# bienTroEncoder.net
KiCad netlist of a schematic drawn in Altium Designer
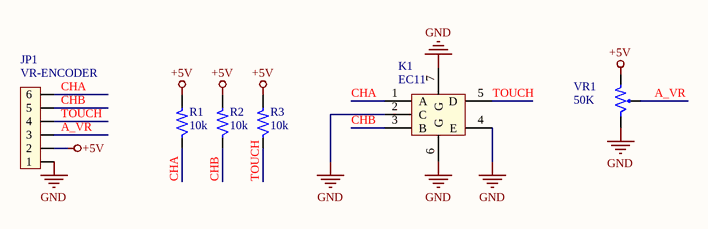
[diagram p0: bienTroEncoder.SchDoc]

(export (version "E")
  (design (tool "Eeschema 10.0.6"))
  (components
    (comp (ref "JP1")
      (value "VR-ENCODER")
      (footprint "JP6")
      (description "JP6 PIN")
      (libsource (lib "syhaunguyen") (part "JP6"))
    )
    (comp (ref "K1") (value "EC11") (libsource (lib "doAnTotNghiep2017Lib") (part "EC11-SW")))
    (comp (ref "R1")
      (value "10k")
      (footprint "R-0805")
      (description "Resistor 1/4W")
      (libsource (lib "PART") (part "R"))
    )
    (comp (ref "R2")
      (value "10k")
      (footprint "R-0805")
      (description "Resistor 1/4W")
      (libsource (lib "PART") (part "R"))
    )
    (comp (ref "R3")
      (value "10k")
      (footprint "R-0805")
      (description "Resistor 1/4W")
      (libsource (lib "PART") (part "R"))
    )
    (comp (ref "VR1") (value "50K") (description "Var Resistor") (libsource (lib "PART") (part "VR1")))
  )
  (nets
    (net (code "1") (name "+5V") (class "Default")
      (node (ref "JP1") (pin "2") (pinfunction "2_2") (pintype "passive"))
      (node (ref "R1") (pin "2") (pinfunction "2_2") (pintype "passive"))
      (node (ref "R2") (pin "2") (pinfunction "2_2") (pintype "passive"))
      (node (ref "R3") (pin "2") (pinfunction "2_2") (pintype "passive"))
      (node (ref "VR1") (pin "1") (pinfunction "1_1") (pintype "passive"))
    )
    (net (code "2") (name "/A_VR") (class "Default")
      (node (ref "JP1") (pin "3") (pinfunction "3_3") (pintype "passive"))
      (node (ref "VR1") (pin "2") (pinfunction "2_2") (pintype "passive"))
    )
    (net (code "3") (name "/CHA") (class "Default")
      (node (ref "JP1") (pin "6") (pinfunction "6_6") (pintype "passive"))
      (node (ref "K1") (pin "1") (pinfunction "A_1") (pintype "passive"))
      (node (ref "R1") (pin "1") (pinfunction "1_1") (pintype "passive"))
    )
    (net (code "4") (name "/CHB") (class "Default")
      (node (ref "JP1") (pin "5") (pinfunction "5_5") (pintype "passive"))
      (node (ref "K1") (pin "3") (pinfunction "B_3") (pintype "passive"))
      (node (ref "R2") (pin "1") (pinfunction "1_1") (pintype "passive"))
    )
    (net (code "5") (name "/TOUCH") (class "Default")
      (node (ref "JP1") (pin "4") (pinfunction "4_4") (pintype "passive"))
      (node (ref "K1") (pin "5") (pinfunction "D_5") (pintype "passive"))
      (node (ref "R3") (pin "1") (pinfunction "1_1") (pintype "passive"))
    )
    (net (code "6") (name "GND") (class "Default")
      (node (ref "JP1") (pin "1") (pinfunction "1_1") (pintype "passive"))
      (node (ref "K1") (pin "2") (pinfunction "C_2") (pintype "passive"))
      (node (ref "K1") (pin "4") (pinfunction "E_4") (pintype "passive"))
      (node (ref "K1") (pin "6") (pinfunction "G_6") (pintype "passive"))
      (node (ref "K1") (pin "7") (pinfunction "G_7") (pintype "passive"))
      (node (ref "VR1") (pin "3") (pinfunction "3_3") (pintype "passive"))
    )
  )
)
